# current_sens.net
KiCad netlist of a schematic drawn in Altium Designer
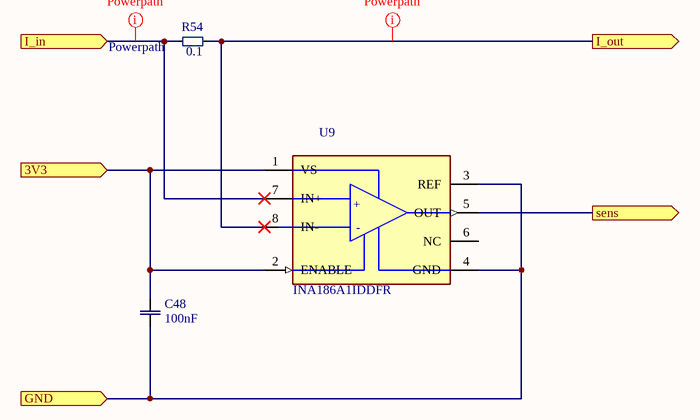
[diagram p0: current_sens.SchDoc]

(export (version "E")
  (design (tool "Eeschema 10.0.6"))
  (components
    (comp (ref "C48")
      (value "GRM155R71H104ME14D")
      (footprint "cap0402")
      (description "0402 0.1 uF 50 V ±20% Tolerance X7R SMT Monolithic Ceramic Chip Capacitor")
      (fields
        (field (name "CAPACITANCE") "100nF")
        (field (name "TOLERANCE") "20%")
        (field (name "LCSC PART#") "C182412")
      )
      (libsource (lib "concord server") (part "Capasitor_keramic_generic"))
    )
    (comp (ref "R54")
      (value "ERJ-8BSFR10V")
      (footprint "Chip2PinSM127P600-8N")
      (fields
        (field (name "RESISTANCE") "0.1")
        (field (name "TOLERANCE") "1%")
        (field (name "LCSC PART#") "C2079636")
      )
      (libsource (lib "concord server") (part "resistor_european"))
    )
    (comp (ref "U9")
      (value "INA186A1IDDFR")
      (footprint "FP-DDF0008A-IPC_C")
      (fields (field (name "LCSC PART#") "C1852082"))
      (libsource (lib "concord server") (part "f4cf8a1e9bb5d369cf5cc6d2fe274b5"))
    )
  )
  (nets
    (net (code "1") (name "/3V3") (class "Default")
      (node (ref "C48") (pin "2") (pinfunction "2_2") (pintype "passive"))
      (node (ref "U9") (pin "1") (pinfunction "VS_1") (pintype "power_in"))
      (node (ref "U9") (pin "2") (pinfunction "ENABLE_2") (pintype "input"))
    )
    (net (code "2") (name "/GND") (class "Default")
      (node (ref "C48") (pin "1") (pinfunction "1_1") (pintype "passive"))
      (node (ref "U9") (pin "3") (pinfunction "REF_3") (pintype "passive"))
      (node (ref "U9") (pin "4") (pinfunction "GND_4") (pintype "power_in"))
    )
    (net (code "3") (name "/I_in") (class "Default")
      (node (ref "R54") (pin "1") (pinfunction "1_1") (pintype "passive"))
      (node (ref "U9") (pin "7") (pinfunction "IN+_7") (pintype "tri_state"))
    )
    (net (code "4") (name "/I_out") (class "Default")
      (node (ref "R54") (pin "2") (pinfunction "2_2") (pintype "passive"))
      (node (ref "U9") (pin "8") (pinfunction "IN-_8") (pintype "tri_state"))
    )
    (net (code "5") (name "/sens") (class "Default")
      (node (ref "U9") (pin "5") (pinfunction "OUT_5") (pintype "output"))
    )
    (net (code "6") (name "unconnected-(U9-NC-Pad6)") (class "Default")
      (node (ref "U9") (pin "6") (pinfunction "NC_6") (pintype "passive"))
    )
  )
)
